# piglow.net
KiCad netlist of a schematic drawn in EAGLE
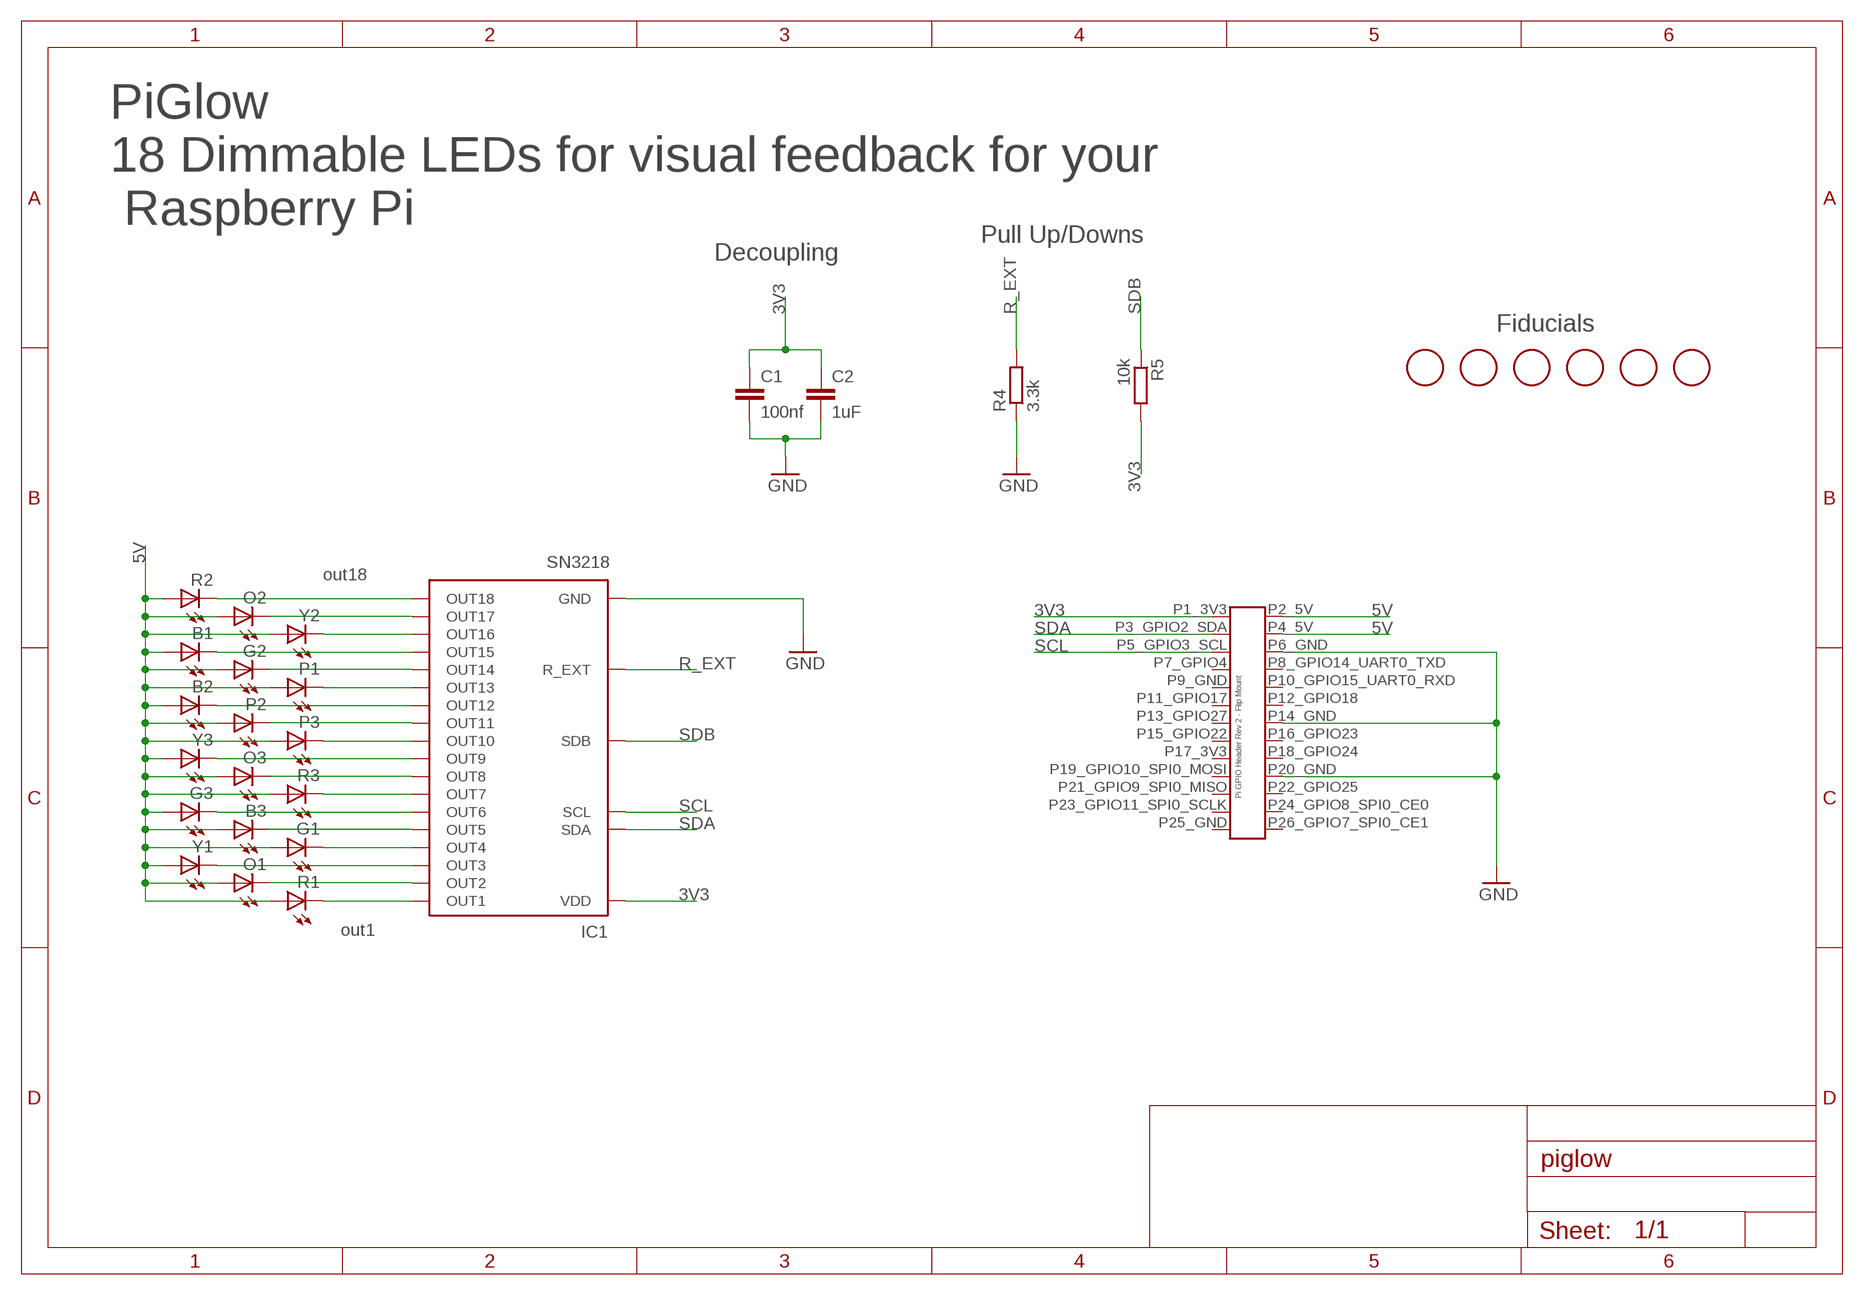
[diagram p0: schematic, sheet 1]

(export (version "E")
  (design (tool "Eeschema 10.0.6"))
  (components
    (comp (ref "B1")
      (value "led-blue-0805")
      (footprint "eagle-import:CHIPLED_0805")
      (libsource (lib "eagle-import") (part "LEDCHIPLED_0805"))
    )
    (comp (ref "B2")
      (value "led-blue-0805")
      (footprint "eagle-import:CHIPLED_0805")
      (libsource (lib "eagle-import") (part "LEDCHIPLED_0805"))
    )
    (comp (ref "B3")
      (value "led-blue-0805")
      (footprint "eagle-import:CHIPLED_0805")
      (libsource (lib "eagle-import") (part "LEDCHIPLED_0805"))
    )
    (comp (ref "C1")
      (value "100nf")
      (footprint "eagle-import:C0603K")
      (libsource (lib "eagle-import") (part "C-EUC0603K"))
    )
    (comp (ref "C2")
      (value "1uF")
      (footprint "eagle-import:C0603K")
      (libsource (lib "eagle-import") (part "C-EUC0603K"))
    )
    (comp (ref "G1")
      (value "led-green-0805")
      (footprint "eagle-import:CHIPLED_0805")
      (libsource (lib "eagle-import") (part "LEDCHIPLED_0805"))
    )
    (comp (ref "G2")
      (value "led-green-0805")
      (footprint "eagle-import:CHIPLED_0805")
      (libsource (lib "eagle-import") (part "LEDCHIPLED_0805"))
    )
    (comp (ref "G3")
      (value "led-green-0805")
      (footprint "eagle-import:CHIPLED_0805")
      (libsource (lib "eagle-import") (part "LEDCHIPLED_0805"))
    )
    (comp (ref "IC1")
      (value "SN3218")
      (footprint "eagle-import:QFN24")
      (libsource (lib "eagle-import") (part "SN3218"))
    )
    (comp (ref "O1")
      (value "led-orange-0805")
      (footprint "eagle-import:CHIPLED_0805")
      (libsource (lib "eagle-import") (part "LEDCHIPLED_0805"))
    )
    (comp (ref "O2")
      (value "led-orange-0805")
      (footprint "eagle-import:CHIPLED_0805")
      (libsource (lib "eagle-import") (part "LEDCHIPLED_0805"))
    )
    (comp (ref "O3")
      (value "led-orange-0805")
      (footprint "eagle-import:CHIPLED_0805")
      (libsource (lib "eagle-import") (part "LEDCHIPLED_0805"))
    )
    (comp (ref "P1")
      (value "led-pink-0805")
      (footprint "eagle-import:CHIPLED_0805")
      (libsource (lib "eagle-import") (part "LEDCHIPLED_0805"))
    )
    (comp (ref "P2")
      (value "led-pink-0805")
      (footprint "eagle-import:CHIPLED_0805")
      (libsource (lib "eagle-import") (part "LEDCHIPLED_0805"))
    )
    (comp (ref "P3")
      (value "led-pink-0805")
      (footprint "eagle-import:CHIPLED_0805")
      (libsource (lib "eagle-import") (part "LEDCHIPLED_0805"))
    )
    (comp (ref "R1")
      (value "led-red-0805")
      (footprint "eagle-import:CHIPLED_0805")
      (libsource (lib "eagle-import") (part "LEDCHIPLED_0805"))
    )
    (comp (ref "R2")
      (value "led-red-0805")
      (footprint "eagle-import:CHIPLED_0805")
      (libsource (lib "eagle-import") (part "LEDCHIPLED_0805"))
    )
    (comp (ref "R3")
      (value "led-red-0805")
      (footprint "eagle-import:CHIPLED_0805")
      (libsource (lib "eagle-import") (part "LEDCHIPLED_0805"))
    )
    (comp (ref "R4")
      (value "3.3k")
      (footprint "eagle-import:R0603")
      (libsource (lib "eagle-import") (part "R-EU_R0603"))
    )
    (comp (ref "R5")
      (value "10k")
      (footprint "eagle-import:R0603@1")
      (libsource (lib "eagle-import") (part "resistor_R-EU_R0603"))
    )
    (comp (ref "U$1")
      (value "FIDUCIAL")
      (footprint "eagle-import:FIDUCIAL_1MM")
      (libsource (lib "eagle-import") (part "FIDUCIAL"))
    )
    (comp (ref "U$2")
      (value "FIDUCIAL")
      (footprint "eagle-import:FIDUCIAL_1MM")
      (libsource (lib "eagle-import") (part "FIDUCIAL"))
    )
    (comp (ref "U$3")
      (value "FIDUCIAL")
      (footprint "eagle-import:FIDUCIAL_1MM")
      (libsource (lib "eagle-import") (part "FIDUCIAL"))
    )
    (comp (ref "U$4")
      (value "FCI_89898_313LF_26P_CONNECTOR_SMT_FLIPPED")
      (footprint "eagle-import:FCI_89898_313LF_26P_CONNECTOR_SMT_FLIPPED")
      (libsource (lib "eagle-import") (part "FCI_89898_313LF_26P_CONNECTOR_SMT_FLIPPED"))
    )
    (comp (ref "U$5")
      (value "FIDUCIAL")
      (footprint "eagle-import:FIDUCIAL_1MM")
      (libsource (lib "eagle-import") (part "FIDUCIAL"))
    )
    (comp (ref "U$6")
      (value "FIDUCIAL")
      (footprint "eagle-import:FIDUCIAL_1MM")
      (libsource (lib "eagle-import") (part "FIDUCIAL"))
    )
    (comp (ref "U$7")
      (value "FIDUCIAL")
      (footprint "eagle-import:FIDUCIAL_1MM")
      (libsource (lib "eagle-import") (part "FIDUCIAL"))
    )
    (comp (ref "Y1")
      (value "led-yellow-0805")
      (footprint "eagle-import:CHIPLED_0805")
      (libsource (lib "eagle-import") (part "LEDCHIPLED_0805"))
    )
    (comp (ref "Y2")
      (value "led-yellow-0805")
      (footprint "eagle-import:CHIPLED_0805")
      (libsource (lib "eagle-import") (part "LEDCHIPLED_0805"))
    )
    (comp (ref "Y3")
      (value "led-yellow-0805")
      (footprint "eagle-import:CHIPLED_0805")
      (libsource (lib "eagle-import") (part "LEDCHIPLED_0805"))
    )
  )
  (nets
    (net (code "1") (name "/3V3") (class "Default")
      (node (ref "C1") (pin "1") (pinfunction "1_1") (pintype "passive"))
      (node (ref "C2") (pin "1") (pinfunction "1_1") (pintype "passive"))
      (node (ref "IC1") (pin "3") (pinfunction "VDD_3") (pintype "bidirectional"))
      (node (ref "R5") (pin "2") (pinfunction "2_2") (pintype "passive"))
      (node (ref "U$4") (pin "P1_3V3") (pinfunction "P1_3V3_P1_3V3") (pintype "power_in"))
    )
    (net (code "2") (name "/5V") (class "Default")
      (node (ref "B1") (pin "A") (pinfunction "A_A") (pintype "passive"))
      (node (ref "B2") (pin "A") (pinfunction "A_A") (pintype "passive"))
      (node (ref "B3") (pin "A") (pinfunction "A_A") (pintype "passive"))
      (node (ref "G1") (pin "A") (pinfunction "A_A") (pintype "passive"))
      (node (ref "G2") (pin "A") (pinfunction "A_A") (pintype "passive"))
      (node (ref "G3") (pin "A") (pinfunction "A_A") (pintype "passive"))
      (node (ref "O1") (pin "A") (pinfunction "A_A") (pintype "passive"))
      (node (ref "O2") (pin "A") (pinfunction "A_A") (pintype "passive"))
      (node (ref "O3") (pin "A") (pinfunction "A_A") (pintype "passive"))
      (node (ref "P1") (pin "A") (pinfunction "A_A") (pintype "passive"))
      (node (ref "P2") (pin "A") (pinfunction "A_A") (pintype "passive"))
      (node (ref "P3") (pin "A") (pinfunction "A_A") (pintype "passive"))
      (node (ref "R1") (pin "A") (pinfunction "A_A") (pintype "passive"))
      (node (ref "R2") (pin "A") (pinfunction "A_A") (pintype "passive"))
      (node (ref "R3") (pin "A") (pinfunction "A_A") (pintype "passive"))
      (node (ref "U$4") (pin "P2_5V") (pinfunction "P2_5V_P2_5V") (pintype "power_in"))
      (node (ref "U$4") (pin "P4_5V") (pinfunction "P4_5V_P4_5V") (pintype "power_in"))
      (node (ref "Y1") (pin "A") (pinfunction "A_A") (pintype "passive"))
      (node (ref "Y2") (pin "A") (pinfunction "A_A") (pintype "passive"))
      (node (ref "Y3") (pin "A") (pinfunction "A_A") (pintype "passive"))
    )
    (net (code "3") (name "/P17_3V3") (class "Default")
      (node (ref "U$4") (pin "P17_3V3") (pinfunction "P17_3V3_P17_3V3") (pintype "power_in"))
    )
    (net (code "4") (name "/R_EXT") (class "Default")
      (node (ref "IC1") (pin "2") (pinfunction "R_EXT_2") (pintype "bidirectional"))
      (node (ref "R4") (pin "2") (pinfunction "2_2") (pintype "passive"))
    )
    (net (code "5") (name "/SCL") (class "Default")
      (node (ref "IC1") (pin "6") (pinfunction "SCL_6") (pintype "bidirectional"))
      (node (ref "U$4") (pin "P5_GPIO3_SCL") (pinfunction "P5_GPIO3_SCL_P5_GPIO3_SCL") (pintype "bidirectional"))
    )
    (net (code "6") (name "/SDA") (class "Default")
      (node (ref "IC1") (pin "5") (pinfunction "SDA_5") (pintype "bidirectional"))
      (node (ref "U$4") (pin "P3_GPIO2_SDA") (pinfunction "P3_GPIO2_SDA_P3_GPIO2_SDA") (pintype "bidirectional"))
    )
    (net (code "7") (name "/SDB") (class "Default")
      (node (ref "IC1") (pin "24") (pinfunction "SDB_24") (pintype "bidirectional"))
      (node (ref "R5") (pin "1") (pinfunction "1_1") (pintype "passive"))
    )
    (net (code "8") (name "GND") (class "Default")
      (node (ref "C1") (pin "2") (pinfunction "2_2") (pintype "passive"))
      (node (ref "C2") (pin "2") (pinfunction "2_2") (pintype "passive"))
      (node (ref "IC1") (pin "4") (pinfunction "GND_4") (pintype "bidirectional"))
      (node (ref "IC1") (pin "GND") (pinfunction "GND_GND") (pintype "bidirectional"))
      (node (ref "R4") (pin "1") (pinfunction "1_1") (pintype "passive"))
      (node (ref "U$4") (pin "P14_GND") (pinfunction "P14_GND_P14_GND") (pintype "passive"))
      (node (ref "U$4") (pin "P20_GND") (pinfunction "P20_GND_P20_GND") (pintype "passive"))
      (node (ref "U$4") (pin "P6_GND") (pinfunction "P6_GND_P6_GND") (pintype "passive"))
    )
    (net (code "9") (name "Net-(IC1-OUT1)") (class "Default")
      (node (ref "IC1") (pin "7") (pinfunction "OUT1_7") (pintype "bidirectional"))
      (node (ref "R1") (pin "C") (pinfunction "C_C") (pintype "passive"))
    )
    (net (code "10") (name "Net-(IC1-OUT2)") (class "Default")
      (node (ref "IC1") (pin "8") (pinfunction "OUT2_8") (pintype "bidirectional"))
      (node (ref "O1") (pin "C") (pinfunction "C_C") (pintype "passive"))
    )
    (net (code "11") (name "Net-(IC1-OUT3)") (class "Default")
      (node (ref "IC1") (pin "9") (pinfunction "OUT3_9") (pintype "bidirectional"))
      (node (ref "Y1") (pin "C") (pinfunction "C_C") (pintype "passive"))
    )
    (net (code "12") (name "Net-(IC1-OUT4)") (class "Default")
      (node (ref "G1") (pin "C") (pinfunction "C_C") (pintype "passive"))
      (node (ref "IC1") (pin "10") (pinfunction "OUT4_10") (pintype "bidirectional"))
    )
    (net (code "13") (name "Net-(IC1-OUT5)") (class "Default")
      (node (ref "B3") (pin "C") (pinfunction "C_C") (pintype "passive"))
      (node (ref "IC1") (pin "11") (pinfunction "OUT5_11") (pintype "bidirectional"))
    )
    (net (code "14") (name "Net-(IC1-OUT6)") (class "Default")
      (node (ref "G3") (pin "C") (pinfunction "C_C") (pintype "passive"))
      (node (ref "IC1") (pin "12") (pinfunction "OUT6_12") (pintype "bidirectional"))
    )
    (net (code "15") (name "Net-(IC1-OUT7)") (class "Default")
      (node (ref "IC1") (pin "13") (pinfunction "OUT7_13") (pintype "bidirectional"))
      (node (ref "R3") (pin "C") (pinfunction "C_C") (pintype "passive"))
    )
    (net (code "16") (name "Net-(IC1-OUT8)") (class "Default")
      (node (ref "IC1") (pin "14") (pinfunction "OUT8_14") (pintype "bidirectional"))
      (node (ref "O3") (pin "C") (pinfunction "C_C") (pintype "passive"))
    )
    (net (code "17") (name "Net-(IC1-OUT9)") (class "Default")
      (node (ref "IC1") (pin "15") (pinfunction "OUT9_15") (pintype "bidirectional"))
      (node (ref "Y3") (pin "C") (pinfunction "C_C") (pintype "passive"))
    )
    (net (code "18") (name "Net-(IC1-OUT10)") (class "Default")
      (node (ref "IC1") (pin "16") (pinfunction "OUT10_16") (pintype "bidirectional"))
      (node (ref "P3") (pin "C") (pinfunction "C_C") (pintype "passive"))
    )
    (net (code "19") (name "Net-(IC1-OUT11)") (class "Default")
      (node (ref "IC1") (pin "17") (pinfunction "OUT11_17") (pintype "bidirectional"))
      (node (ref "P2") (pin "C") (pinfunction "C_C") (pintype "passive"))
    )
    (net (code "20") (name "Net-(IC1-OUT12)") (class "Default")
      (node (ref "B2") (pin "C") (pinfunction "C_C") (pintype "passive"))
      (node (ref "IC1") (pin "18") (pinfunction "OUT12_18") (pintype "bidirectional"))
    )
    (net (code "21") (name "Net-(IC1-OUT13)") (class "Default")
      (node (ref "IC1") (pin "19") (pinfunction "OUT13_19") (pintype "bidirectional"))
      (node (ref "P1") (pin "C") (pinfunction "C_C") (pintype "passive"))
    )
    (net (code "22") (name "Net-(IC1-OUT14)") (class "Default")
      (node (ref "G2") (pin "C") (pinfunction "C_C") (pintype "passive"))
      (node (ref "IC1") (pin "20") (pinfunction "OUT14_20") (pintype "bidirectional"))
    )
    (net (code "23") (name "Net-(IC1-OUT15)") (class "Default")
      (node (ref "B1") (pin "C") (pinfunction "C_C") (pintype "passive"))
      (node (ref "IC1") (pin "21") (pinfunction "OUT15_21") (pintype "bidirectional"))
    )
    (net (code "24") (name "Net-(IC1-OUT16)") (class "Default")
      (node (ref "IC1") (pin "22") (pinfunction "OUT16_22") (pintype "bidirectional"))
      (node (ref "Y2") (pin "C") (pinfunction "C_C") (pintype "passive"))
    )
    (net (code "25") (name "Net-(IC1-OUT17)") (class "Default")
      (node (ref "IC1") (pin "23") (pinfunction "OUT17_23") (pintype "bidirectional"))
      (node (ref "O2") (pin "C") (pinfunction "C_C") (pintype "passive"))
    )
    (net (code "26") (name "Net-(IC1-OUT18)") (class "Default")
      (node (ref "IC1") (pin "1") (pinfunction "OUT18_1") (pintype "bidirectional"))
      (node (ref "R2") (pin "C") (pinfunction "C_C") (pintype "passive"))
    )
    (net (code "27") (name "unconnected-(U$4-PadP7_GPIO4)") (class "Default")
      (node (ref "U$4") (pin "P7_GPIO4") (pinfunction "P7_GPIO4_P7_GPIO4") (pintype "bidirectional"))
    )
    (net (code "28") (name "unconnected-(U$4-PadP8_GPIO14_UART0_TXD)") (class "Default")
      (node (ref "U$4") (pin "P8_GPIO14_UART0_TXD") (pinfunction "P8_GPIO14_UART0_TXD_P8_GPIO14_UART0_TXD") (pintype "bidirectional"))
    )
    (net (code "29") (name "unconnected-(U$4-PadP9_GND)") (class "Default")
      (node (ref "U$4") (pin "P9_GND") (pinfunction "P9_GND_P9_GND") (pintype "passive"))
    )
    (net (code "30") (name "unconnected-(U$4-PadP10_GPIO15_UART0_RXD)") (class "Default")
      (node (ref "U$4") (pin "P10_GPIO15_UART0_RXD") (pinfunction "P10_GPIO15_UART0_RXD_P10_GPIO15_UART0_RXD") (pintype "bidirectional"))
    )
    (net (code "31") (name "unconnected-(U$4-PadP11_GPIO17)") (class "Default")
      (node (ref "U$4") (pin "P11_GPIO17") (pinfunction "P11_GPIO17_P11_GPIO17") (pintype "bidirectional"))
    )
    (net (code "32") (name "unconnected-(U$4-PadP12_GPIO18)") (class "Default")
      (node (ref "U$4") (pin "P12_GPIO18") (pinfunction "P12_GPIO18_P12_GPIO18") (pintype "bidirectional"))
    )
    (net (code "33") (name "unconnected-(U$4-PadP13_GPIO27)") (class "Default")
      (node (ref "U$4") (pin "P13_GPIO27") (pinfunction "P13_GPIO27_P13_GPIO27") (pintype "bidirectional"))
    )
    (net (code "34") (name "unconnected-(U$4-PadP15_GPIO22)") (class "Default")
      (node (ref "U$4") (pin "P15_GPIO22") (pinfunction "P15_GPIO22_P15_GPIO22") (pintype "bidirectional"))
    )
    (net (code "35") (name "unconnected-(U$4-PadP16_GPIO23)") (class "Default")
      (node (ref "U$4") (pin "P16_GPIO23") (pinfunction "P16_GPIO23_P16_GPIO23") (pintype "bidirectional"))
    )
    (net (code "36") (name "unconnected-(U$4-PadP18_GPIO24)") (class "Default")
      (node (ref "U$4") (pin "P18_GPIO24") (pinfunction "P18_GPIO24_P18_GPIO24") (pintype "bidirectional"))
    )
    (net (code "37") (name "unconnected-(U$4-PadP19_GPIO10_SPI0_MOSI)") (class "Default")
      (node (ref "U$4") (pin "P19_GPIO10_SPI0_MOSI") (pinfunction "P19_GPIO10_SPI0_MOSI_P19_GPIO10_SPI0_MOSI") (pintype "bidirectional"))
    )
    (net (code "38") (name "unconnected-(U$4-PadP21_GPIO9_SPI0_MISO)") (class "Default")
      (node (ref "U$4") (pin "P21_GPIO9_SPI0_MISO") (pinfunction "P21_GPIO9_SPI0_MISO_P21_GPIO9_SPI0_MISO") (pintype "bidirectional"))
    )
    (net (code "39") (name "unconnected-(U$4-PadP22_GPIO25)") (class "Default")
      (node (ref "U$4") (pin "P22_GPIO25") (pinfunction "P22_GPIO25_P22_GPIO25") (pintype "bidirectional"))
    )
    (net (code "40") (name "unconnected-(U$4-PadP23_GPIO11_SPI0_SCLK)") (class "Default")
      (node (ref "U$4") (pin "P23_GPIO11_SPI0_SCLK") (pinfunction "P23_GPIO11_SPI0_SCLK_P23_GPIO11_SPI0_SCLK") (pintype "bidirectional"))
    )
    (net (code "41") (name "unconnected-(U$4-PadP24_GPIO8_SPI0_CE0)") (class "Default")
      (node (ref "U$4") (pin "P24_GPIO8_SPI0_CE0") (pinfunction "P24_GPIO8_SPI0_CE0_P24_GPIO8_SPI0_CE0") (pintype "bidirectional"))
    )
    (net (code "42") (name "unconnected-(U$4-PadP25_GND)") (class "Default")
      (node (ref "U$4") (pin "P25_GND") (pinfunction "P25_GND_P25_GND") (pintype "passive"))
    )
    (net (code "43") (name "unconnected-(U$4-PadP26_GPIO7_SPI0_CE1)") (class "Default")
      (node (ref "U$4") (pin "P26_GPIO7_SPI0_CE1") (pinfunction "P26_GPIO7_SPI0_CE1_P26_GPIO7_SPI0_CE1") (pintype "bidirectional"))
    )
  )
)
